# CH32F103C-R1.net
KiCad netlist of a schematic drawn in Altium Designer
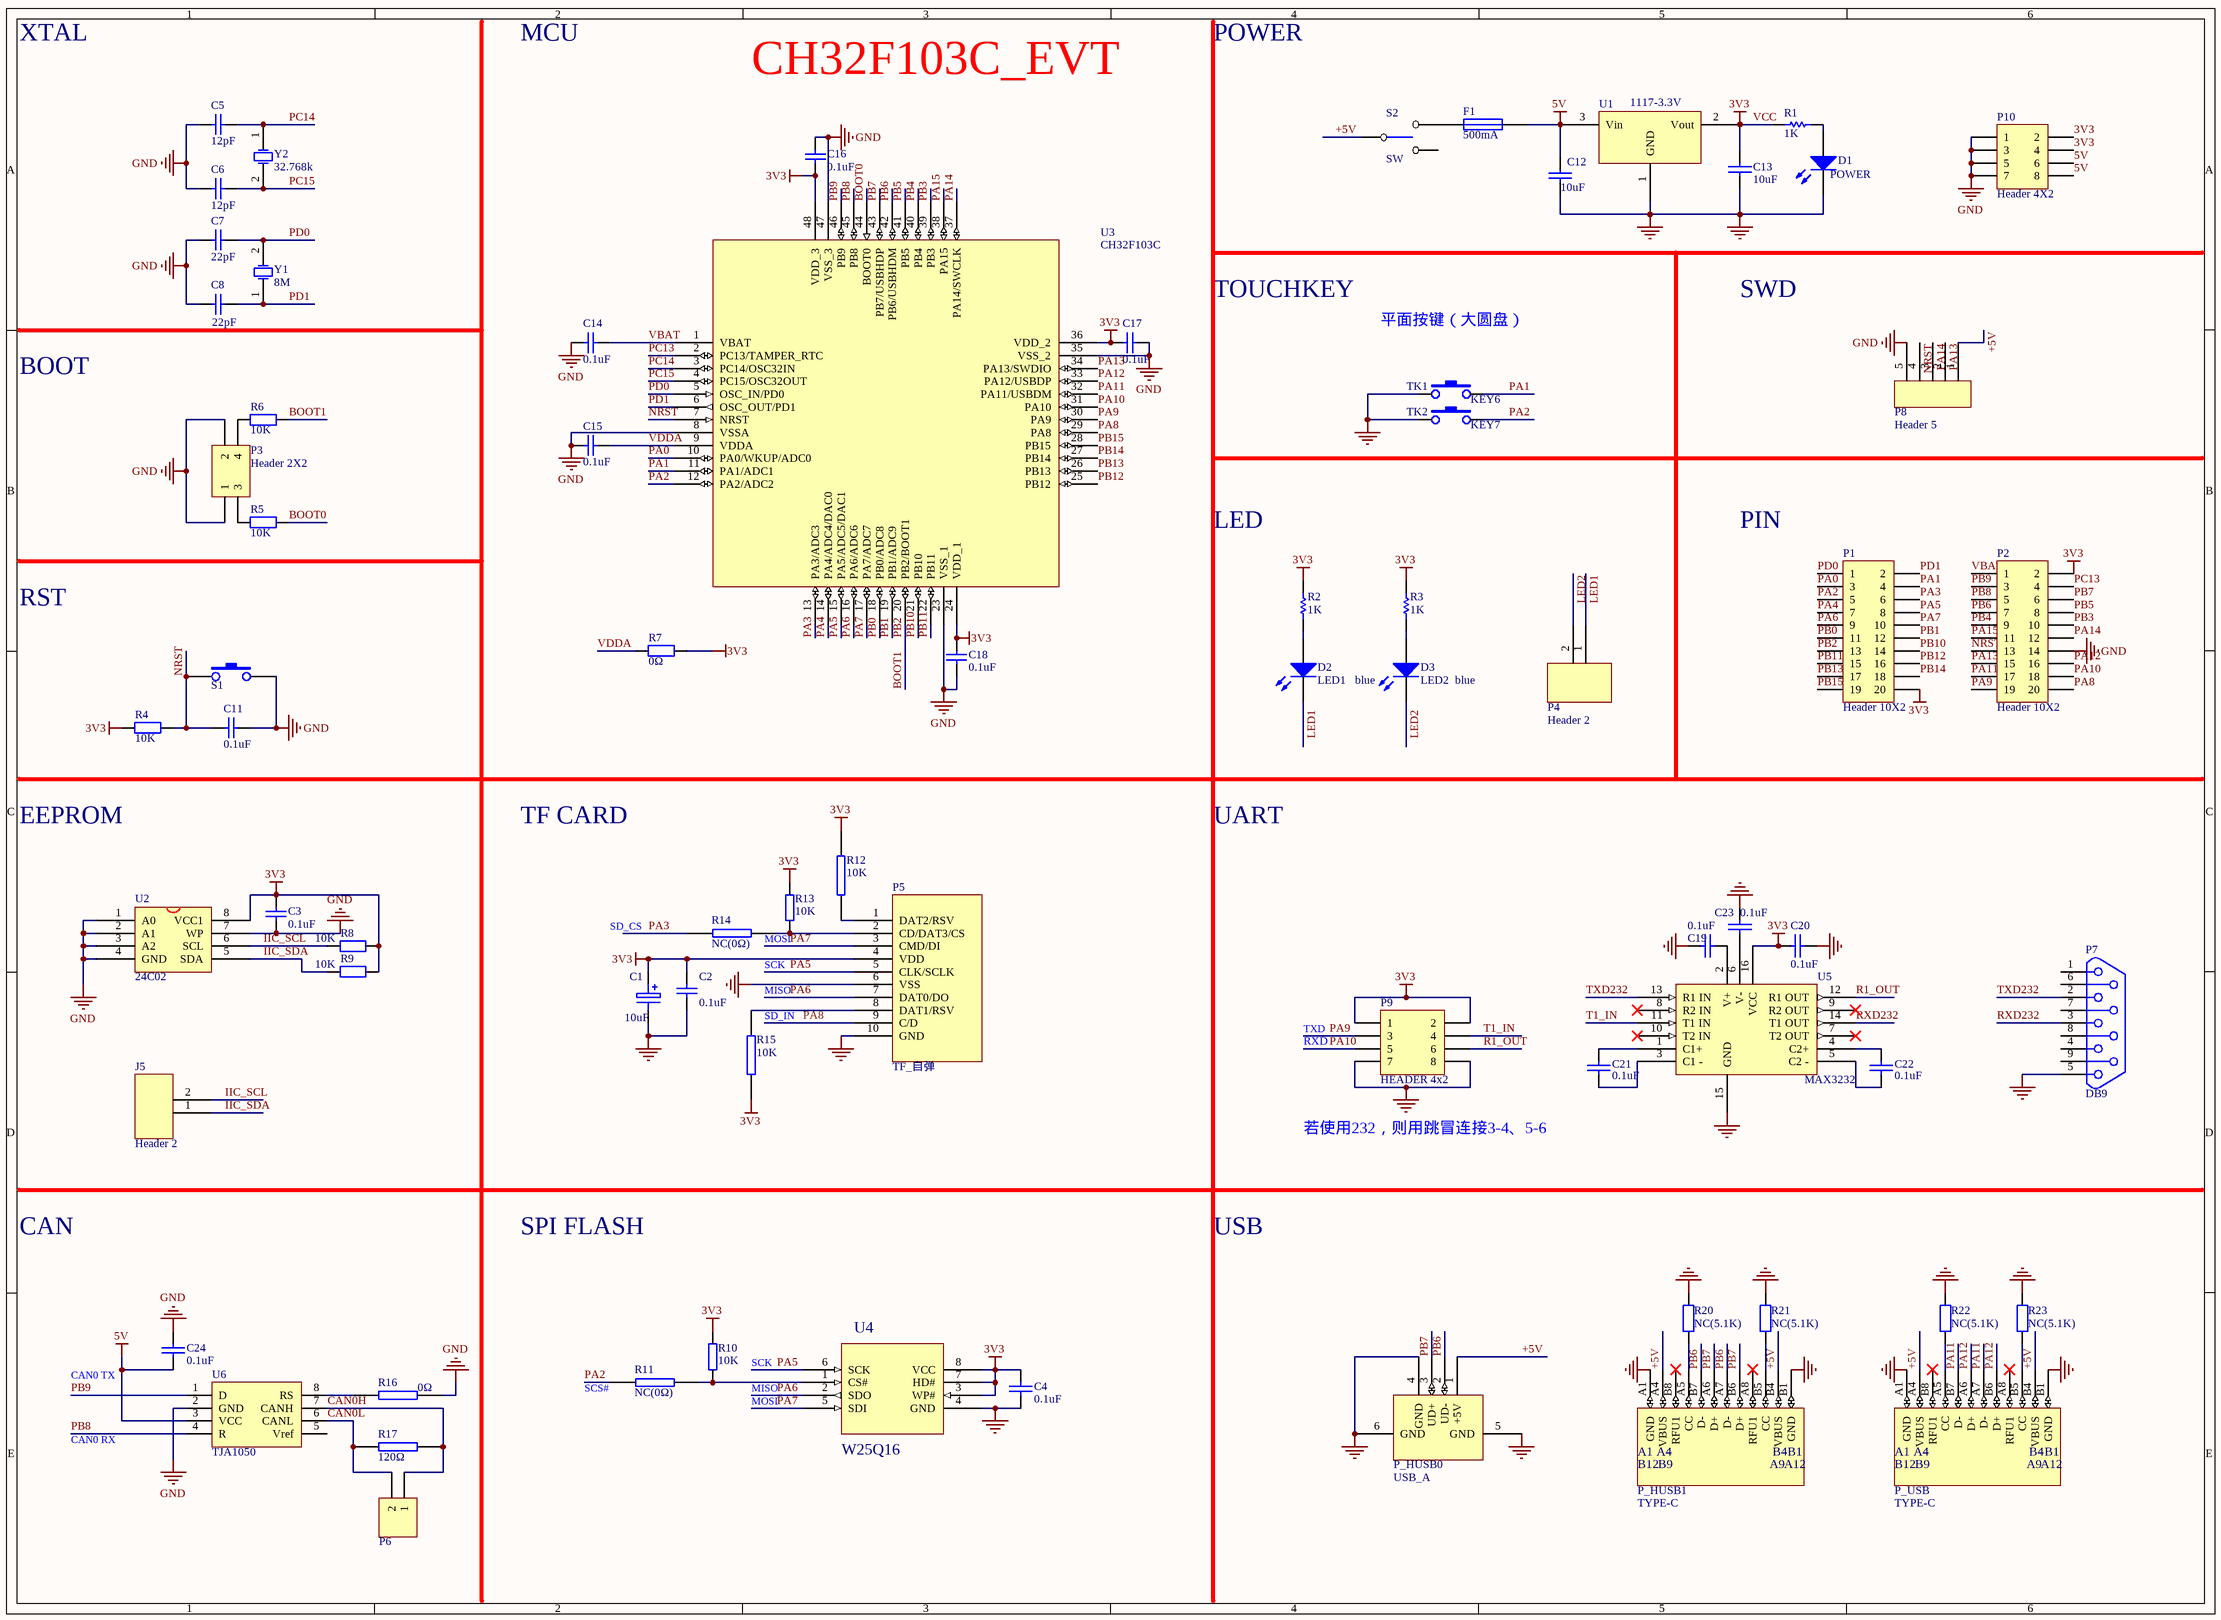
[diagram p0: CH32F103C-R1.SchDoc]

(export (version "E")
  (design (tool "Eeschema 10.0.6"))
  (components
    (comp (ref "C1")
      (value "10uF")
      (footprint "3216")
      (description "Electrolytic Capacitor")
      (libsource (lib "*") (part "ELECTRO1"))
    )
    (comp (ref "C2")
      (value "0.1uF")
      (footprint "0603")
      (description "Capacitor")
      (fields (field (name "PUBLISHER") "Altium Limited"))
      (libsource (lib "*") (part "Cap"))
    )
    (comp (ref "C3")
      (value "0.1uF")
      (footprint "0603")
      (description "Capacitor")
      (fields (field (name "PUBLISHER") "Altium Limited"))
      (libsource (lib "Miscellaneous Devices") (part "Cap"))
    )
    (comp (ref "C4")
      (value "0.1uF")
      (footprint "0603")
      (description "Capacitor")
      (libsource (lib "") (part "CAP_1"))
    )
    (comp (ref "C5")
      (value "12pF")
      (footprint "0603")
      (description "Capacitor")
      (fields (field (name "PUBLISHER") "Altium Limited"))
      (libsource (lib "Miscellaneous Devices") (part "Cap"))
    )
    (comp (ref "C6")
      (value "12pF")
      (footprint "0603")
      (description "Capacitor")
      (fields (field (name "PUBLISHER") "Altium Limited"))
      (libsource (lib "Miscellaneous Devices") (part "Cap"))
    )
    (comp (ref "C7")
      (value "22pF")
      (footprint "0603")
      (description "Capacitor")
      (fields (field (name "PUBLISHER") "Altium Limited"))
      (libsource (lib "Miscellaneous Devices") (part "Cap"))
    )
    (comp (ref "C8")
      (value "22pF")
      (footprint "0603")
      (description "Capacitor")
      (fields (field (name "PUBLISHER") "Altium Limited"))
      (libsource (lib "Miscellaneous Devices") (part "Cap"))
    )
    (comp (ref "C11")
      (value "0.1uF")
      (footprint "0603")
      (description "Capacitor")
      (fields (field (name "PUBLISHER") "Altium Limited"))
      (libsource (lib "Miscellaneous Devices") (part "Cap"))
    )
    (comp (ref "C12")
      (value "10uF")
      (footprint "3216")
      (description "Capacitor")
      (libsource (lib "*") (part "CAP"))
    )
    (comp (ref "C13")
      (value "10uF")
      (footprint "0603")
      (description "Capacitor")
      (libsource (lib "*") (part "CAP"))
    )
    (comp (ref "C14")
      (value "0.1uF")
      (footprint "0603")
      (description "Capacitor")
      (fields (field (name "PUBLISHER") "Altium Limited"))
      (libsource (lib "Miscellaneous Devices") (part "Cap"))
    )
    (comp (ref "C15")
      (value "0.1uF")
      (footprint "0603")
      (description "Capacitor")
      (fields (field (name "PUBLISHER") "Altium Limited"))
      (libsource (lib "Miscellaneous Devices") (part "Cap"))
    )
    (comp (ref "C16")
      (value "0.1uF")
      (footprint "0603")
      (description "Capacitor")
      (fields (field (name "PUBLISHER") "Altium Limited"))
      (libsource (lib "Miscellaneous Devices") (part "Cap"))
    )
    (comp (ref "C17")
      (value "0.1uF")
      (footprint "0603")
      (description "Capacitor")
      (fields (field (name "PUBLISHER") "Altium Limited"))
      (libsource (lib "Miscellaneous Devices") (part "Cap"))
    )
    (comp (ref "C18")
      (value "0.1uF")
      (footprint "0603")
      (description "Capacitor")
      (fields (field (name "PUBLISHER") "Altium Limited"))
      (libsource (lib "Miscellaneous Devices") (part "Cap"))
    )
    (comp (ref "C19")
      (value "0.1uF")
      (footprint "0603")
      (description "Capacitor")
      (libsource (lib "") (part "CAP_1"))
    )
    (comp (ref "C20")
      (value "0.1uF")
      (footprint "0603")
      (description "Capacitor")
      (libsource (lib "") (part "CAP_1"))
    )
    (comp (ref "C21")
      (value "0.1uF")
      (footprint "0603")
      (description "Capacitor")
      (libsource (lib "") (part "CAP_1"))
    )
    (comp (ref "C22")
      (value "0.1uF")
      (footprint "0603")
      (description "Capacitor")
      (libsource (lib "") (part "CAP_1"))
    )
    (comp (ref "C23")
      (value "0.1uF")
      (footprint "0603")
      (description "Capacitor")
      (libsource (lib "") (part "CAP_1"))
    )
    (comp (ref "C24")
      (value "0.1uF")
      (footprint "0603")
      (description "Capacitor")
      (libsource (lib "") (part "CAP_1"))
    )
    (comp (ref "D1")
      (value "POWER")
      (footprint "0603L")
      (description "Typical INFRARED GaAs LED")
      (fields (field (name "PUBLISHER") "Altium Limited"))
      (libsource (lib "Miscellaneous Devices") (part "LED0"))
    )
    (comp (ref "D2")
      (value "LED1   blue")
      (footprint "0603L")
      (description "Typical INFRARED GaAs LED")
      (fields (field (name "PUBLISHER") "Altium Limited"))
      (libsource (lib "Miscellaneous Devices") (part "LED0"))
    )
    (comp (ref "D3")
      (value "LED2  blue")
      (footprint "0603L")
      (description "Typical INFRARED GaAs LED")
      (fields (field (name "PUBLISHER") "Altium Limited"))
      (libsource (lib "Miscellaneous Devices") (part "LED0"))
    )
    (comp (ref "F1")
      (value "500mA")
      (footprint "0603")
      (description "Fuse")
      (libsource (lib "*") (part "FUSE1"))
    )
    (comp (ref "J5") (value "Header 2") (footprint "SIP2 - 40mil") (libsource (lib "") (part "2HEAD_1")))
    (comp (ref "P1")
      (value "Header 10X2")
      (footprint "IDC20")
      (description "Header, 10-Pin, Dual row")
      (fields (field (name "PUBLISHER") "Altium Limited"))
      (libsource (lib "Miscellaneous Connectors") (part "Header 10X2"))
    )
    (comp (ref "P2")
      (value "Header 10X2")
      (footprint "IDC20")
      (description "Header, 10-Pin, Dual row")
      (fields (field (name "PUBLISHER") "Altium Limited"))
      (libsource (lib "Miscellaneous Connectors") (part "Header 10X2"))
    )
    (comp (ref "P3")
      (value "Header 2X2")
      (footprint "HDR2X2")
      (description "Header, 2-Pin, Dual row")
      (fields (field (name "PUBLISHER") "Altium Limited"))
      (libsource (lib "Miscellaneous Connectors") (part "Header 2X2"))
    )
    (comp (ref "P4") (value "Header 2") (footprint "SIP2 - 40mil") (libsource (lib "MYSCH") (part "2HEAD")))
    (comp (ref "P5") (value "TF_自弹") (footprint "TF_CARD") (libsource (lib "*") (part "TF_自弹")))
    (comp (ref "P6")
      (value "Header 2")
      (footprint "PORT2 4.5MM")
      (description "Header, 2-Pin")
      (fields (field (name "PUBLISHER") "Altium Limited"))
      (libsource (lib "Miscellaneous Connectors") (part "Header 2"))
    )
    (comp (ref "P7") (value "DB9") (footprint "DB9") (libsource (lib "*") (part "DB9")))
    (comp (ref "P8")
      (value "Header 5")
      (footprint "SIP5 - 40mil")
      (libsource (lib "PCB_Project1") (part "2HEAD"))
    )
    (comp (ref "P9")
      (value "HEADER 4x2")
      (footprint "MYPCB:IDC8-2.54mm")
      (description "Header, 4-Pin, Dual row")
      (libsource (lib "wch_sch_others") (part "HEADER 4x2"))
    )
    (comp (ref "P10")
      (value "Header 4X2")
      (footprint "IDC8")
      (description "Header, 4-Pin, Dual row")
      (fields (field (name "PUBLISHER") "Altium Limited"))
      (libsource (lib "Miscellaneous Connectors") (part "Header 4X2"))
    )
    (comp (ref "P_HUSB0")
      (value "USB_A")
      (footprint "USBA-l")
      (description "USB Port")
      (libsource (lib "CHXXXSCH") (part "USB"))
    )
    (comp (ref "P_HUSB1")
      (value "TYPE-C")
      (footprint "TYPE-C-Receptacle-2.0")
      (libsource (lib "*") (part "TYPE-C1"))
    )
    (comp (ref "P_USB")
      (value "TYPE-C")
      (footprint "TYPE-C-Receptacle-2.0")
      (libsource (lib "*") (part "TYPE-C1"))
    )
    (comp (ref "R1")
      (value "1K")
      (footprint "0603")
      (description "Semiconductor Resistor")
      (fields (field (name "PUBLISHER") "Altium Limited"))
      (libsource (lib "Miscellaneous Devices") (part "Res Semi"))
    )
    (comp (ref "R2")
      (value "1K")
      (footprint "0603")
      (description "Semiconductor Resistor")
      (fields (field (name "PUBLISHER") "Altium Limited"))
      (libsource (lib "Miscellaneous Devices") (part "Res Semi"))
    )
    (comp (ref "R3")
      (value "1K")
      (footprint "0603")
      (description "Semiconductor Resistor")
      (fields (field (name "PUBLISHER") "Altium Limited"))
      (libsource (lib "Miscellaneous Devices") (part "Res Semi"))
    )
    (comp (ref "R4")
      (value "10K")
      (footprint "0603")
      (description "Resistor")
      (fields (field (name "PUBLISHER") "Altium Limited"))
      (libsource (lib "") (part "Res2_1"))
    )
    (comp (ref "R5")
      (value "10K")
      (footprint "0603")
      (description "Resistor")
      (fields (field (name "PUBLISHER") "Altium Limited"))
      (libsource (lib "") (part "Res2_1"))
    )
    (comp (ref "R6")
      (value "10K")
      (footprint "0603")
      (description "Resistor")
      (fields (field (name "PUBLISHER") "Altium Limited"))
      (libsource (lib "") (part "Res2_1"))
    )
    (comp (ref "R7")
      (value "0Ω")
      (footprint "0603")
      (description "Resistor")
      (fields (field (name "PUBLISHER") "Altium Limited"))
      (libsource (lib "") (part "Res2_1"))
    )
    (comp (ref "R8")
      (value "10K")
      (footprint "0603")
      (description "Resistor")
      (fields (field (name "PUBLISHER") "Altium Limited"))
      (libsource (lib "") (part "Res2_1"))
    )
    (comp (ref "R9")
      (value "10K")
      (footprint "0603")
      (description "Resistor")
      (fields (field (name "PUBLISHER") "Altium Limited"))
      (libsource (lib "") (part "Res2_1"))
    )
    (comp (ref "R10") (value "10K") (footprint "0603") (libsource (lib "*") (part "DZ")))
    (comp (ref "R11") (value "NC(0Ω)") (footprint "0603") (libsource (lib "*") (part "RES2")))
    (comp (ref "R12") (value "10K") (footprint "0603") (libsource (lib "*") (part "RES2")))
    (comp (ref "R13") (value "10K") (footprint "0603") (libsource (lib "*") (part "DZ")))
    (comp (ref "R14") (value "NC(0Ω)") (footprint "0603") (libsource (lib "*") (part "RES2")))
    (comp (ref "R15") (value "10K") (footprint "0603") (libsource (lib "*") (part "RES2")))
    (comp (ref "R16") (value "0Ω") (footprint "0603") (libsource (lib "*") (part "RES2")))
    (comp (ref "R17") (value "120Ω") (footprint "0603") (libsource (lib "*") (part "RES2")))
    (comp (ref "R20")
      (value "NC(5.1K)")
      (footprint "0603")
      (description "Resistor")
      (libsource (lib "Miscellaneous Devices") (part "Res2"))
    )
    (comp (ref "R21")
      (value "NC(5.1K)")
      (footprint "0603")
      (description "Resistor")
      (libsource (lib "Miscellaneous Devices") (part "Res2"))
    )
    (comp (ref "R22")
      (value "NC(5.1K)")
      (footprint "0603")
      (description "Resistor")
      (libsource (lib "Miscellaneous Devices") (part "Res2"))
    )
    (comp (ref "R23")
      (value "NC(5.1K)")
      (footprint "0603")
      (description "Resistor")
      (libsource (lib "Miscellaneous Devices") (part "Res2"))
    )
    (comp (ref "S1") (value "KEY") (footprint "贴片按键") (libsource (lib "CCDXPLIB") (part "KEY")))
    (comp (ref "S2") (value "SW") (footprint "KEY2") (libsource (lib "MYSCH") (part "SW")))
    (comp (ref "TK1") (value "KEY6") (footprint "KEY68") (libsource (lib "*") (part "KEY")))
    (comp (ref "TK2") (value "KEY7") (footprint "KEY68") (libsource (lib "*") (part "KEY")))
    (comp (ref "U1")
      (value "1117-3.3V")
      (footprint "SOT-223")
      (libsource (lib "wch_sch_others") (part "1117-3.3V"))
    )
    (comp (ref "U2") (value "24C02") (footprint "SOP8") (libsource (lib "Elite_SCH") (part "24C256")))
    (comp (ref "U3")
      (value "CH32F103C")
      (footprint "LQFP48")
      (description "ARM M3 MCU with USB device & USB host & ADC & 12bit DAC & Touch Key & CAN")
      (libsource (lib "CHXXX") (part "CH32F103C"))
    )
    (comp (ref "U4")
      (value "W25Q16")
      (footprint "016 SO-8")
      (libsource (lib "*") (part "Pro89C.tmp_25F512_2"))
    )
    (comp (ref "U5")
      (value "MAX3232")
      (footprint "SO-16")
      (description "+-15KV ESD-PROTECTED, +5V RS-232 TRANSCEIVERS")
      (libsource (lib "*") (part "MAX232CPE(16)"))
    )
    (comp (ref "U6") (value "TJA1050") (footprint "SOP8") (libsource (lib "CAN") (part "Component_1")))
    (comp (ref "Y1")
      (value "8M")
      (footprint "XT62/28")
      (description "Crystal Oscillator")
      (fields (field (name "PUBLISHER") "Altium Limited"))
      (libsource (lib "Miscellaneous Devices") (part "XTAL"))
    )
    (comp (ref "Y2")
      (value "32.768k")
      (footprint "FC-135")
      (description "Crystal Oscillator")
      (fields (field (name "PUBLISHER") "Altium Limited"))
      (libsource (lib "Miscellaneous Devices") (part "XTAL"))
    )
  )
  (nets
    (net (code "1") (name "/+5V") (class "Default")
      (node (ref "P8") (pin "1") (pintype "passive"))
      (node (ref "P_HUSB0") (pin "1") (pinfunction "+5V_1") (pintype "power_in"))
      (node (ref "P_HUSB1") (pin "A4") (pinfunction "VBUS_A4") (pintype "bidirectional"))
      (node (ref "P_HUSB1") (pin "B4") (pinfunction "VBUS_B4") (pintype "bidirectional"))
      (node (ref "P_USB") (pin "A4") (pinfunction "VBUS_A4") (pintype "bidirectional"))
      (node (ref "P_USB") (pin "B4") (pinfunction "VBUS_B4") (pintype "bidirectional"))
      (node (ref "S2") (pin "1") (pinfunction "1_1") (pintype "passive"))
    )
    (net (code "3") (name "/BOOT0") (class "Default")
      (node (ref "R5") (pin "1") (pinfunction "1_1") (pintype "passive"))
      (node (ref "U3") (pin "44") (pinfunction "BOOT0_44") (pintype "input"))
    )
    (net (code "4") (name "/BOOT1") (class "Default")
      (node (ref "P1") (pin "13") (pinfunction "13_13") (pintype "passive"))
      (node (ref "R6") (pin "1") (pinfunction "1_1") (pintype "passive"))
      (node (ref "U3") (pin "20") (pinfunction "PB2/BOOT1_20") (pintype "bidirectional"))
    )
    (net (code "5") (name "/CAN0H") (class "Default")
      (node (ref "P6") (pin "1") (pinfunction "1_1") (pintype "passive"))
      (node (ref "R17") (pin "1") (pinfunction "1_1") (pintype "passive"))
      (node (ref "U6") (pin "7") (pinfunction "CANH_7") (pintype "passive"))
    )
    (net (code "6") (name "/CAN0L") (class "Default")
      (node (ref "P6") (pin "2") (pinfunction "2_2") (pintype "passive"))
      (node (ref "R17") (pin "2") (pinfunction "2_2") (pintype "passive"))
      (node (ref "U6") (pin "6") (pinfunction "CANL_6") (pintype "passive"))
    )
    (net (code "7") (name "/IIC_SCL") (class "Default")
      (node (ref "J5") (pin "2") (pintype "passive"))
      (node (ref "R8") (pin "2") (pinfunction "2_2") (pintype "passive"))
      (node (ref "U2") (pin "6") (pinfunction "SCL_6") (pintype "passive"))
    )
    (net (code "8") (name "/IIC_SDA") (class "Default")
      (node (ref "J5") (pin "1") (pintype "passive"))
      (node (ref "R9") (pin "2") (pinfunction "2_2") (pintype "passive"))
      (node (ref "U2") (pin "5") (pinfunction "SDA_5") (pintype "passive"))
    )
    (net (code "9") (name "/LED1") (class "Default")
      (node (ref "D2") (pin "2") (pinfunction "K_2") (pintype "passive"))
      (node (ref "P4") (pin "1") (pintype "passive"))
    )
    (net (code "10") (name "/LED2") (class "Default")
      (node (ref "D3") (pin "2") (pinfunction "K_2") (pintype "passive"))
      (node (ref "P4") (pin "2") (pintype "passive"))
    )
    (net (code "11") (name "/NRST") (class "Default")
      (node (ref "C11") (pin "2") (pinfunction "2_2") (pintype "passive"))
      (node (ref "P2") (pin "13") (pinfunction "13_13") (pintype "passive"))
      (node (ref "P8") (pin "4") (pintype "passive"))
      (node (ref "R4") (pin "1") (pinfunction "1_1") (pintype "passive"))
      (node (ref "S1") (pin "1") (pinfunction "1_1") (pintype "passive"))
      (node (ref "U3") (pin "7") (pinfunction "NRST_7") (pintype "input"))
    )
    (net (code "12") (name "/PA0") (class "Default")
      (node (ref "P1") (pin "3") (pinfunction "3_3") (pintype "passive"))
      (node (ref "U3") (pin "10") (pinfunction "PA0/WKUP/ADC0_10") (pintype "bidirectional"))
    )
    (net (code "13") (name "/PA1") (class "Default")
      (node (ref "P1") (pin "4") (pinfunction "4_4") (pintype "passive"))
      (node (ref "TK1") (pin "1") (pintype "passive"))
      (node (ref "U3") (pin "11") (pinfunction "PA1/ADC1_11") (pintype "bidirectional"))
    )
    (net (code "14") (name "/PA2") (class "Default")
      (node (ref "P1") (pin "5") (pinfunction "5_5") (pintype "passive"))
      (node (ref "R11") (pin "2") (pinfunction "2_2") (pintype "passive"))
      (node (ref "TK2") (pin "1") (pintype "passive"))
      (node (ref "U3") (pin "12") (pinfunction "PA2/ADC2_12") (pintype "bidirectional"))
    )
    (net (code "15") (name "/PA3") (class "Default")
      (node (ref "P1") (pin "6") (pinfunction "6_6") (pintype "passive"))
      (node (ref "R14") (pin "2") (pinfunction "2_2") (pintype "passive"))
      (node (ref "U3") (pin "13") (pinfunction "PA3/ADC3_13") (pintype "bidirectional"))
    )
    (net (code "16") (name "/PA4") (class "Default")
      (node (ref "P1") (pin "7") (pinfunction "7_7") (pintype "passive"))
      (node (ref "U3") (pin "14") (pinfunction "PA4/ADC4/DAC0_14") (pintype "bidirectional"))
    )
    (net (code "17") (name "/PA5") (class "Default")
      (node (ref "P1") (pin "8") (pinfunction "8_8") (pintype "passive"))
      (node (ref "P5") (pin "5") (pinfunction "CLK/SCLK_5") (pintype "passive"))
      (node (ref "U3") (pin "15") (pinfunction "PA5/ADC5/DAC1_15") (pintype "bidirectional"))
      (node (ref "U4") (pin "6") (pinfunction "SCK_6") (pintype "input"))
    )
    (net (code "18") (name "/PA6") (class "Default")
      (node (ref "P1") (pin "9") (pinfunction "9_9") (pintype "passive"))
      (node (ref "P5") (pin "7") (pinfunction "DAT0/DO_7") (pintype "passive"))
      (node (ref "U3") (pin "16") (pinfunction "PA6/ADC6_16") (pintype "bidirectional"))
      (node (ref "U4") (pin "2") (pinfunction "SDO_2") (pintype "output"))
    )
    (net (code "19") (name "/PA7") (class "Default")
      (node (ref "P1") (pin "10") (pinfunction "10_10") (pintype "passive"))
      (node (ref "P5") (pin "3") (pinfunction "CMD/DI_3") (pintype "passive"))
      (node (ref "U3") (pin "17") (pinfunction "PA7/ADC7_17") (pintype "bidirectional"))
      (node (ref "U4") (pin "5") (pinfunction "SDI_5") (pintype "input"))
    )
    (net (code "20") (name "/PA8") (class "Default")
      (node (ref "P2") (pin "20") (pinfunction "20_20") (pintype "passive"))
      (node (ref "P5") (pin "9") (pinfunction "C/D_9") (pintype "passive"))
      (node (ref "U3") (pin "29") (pinfunction "PA8_29") (pintype "bidirectional"))
    )
    (net (code "21") (name "/PA9") (class "Default")
      (node (ref "P2") (pin "19") (pinfunction "19_19") (pintype "passive"))
      (node (ref "P9") (pin "3") (pinfunction "3_3") (pintype "passive"))
      (node (ref "U3") (pin "30") (pinfunction "PA9_30") (pintype "bidirectional"))
    )
    (net (code "22") (name "/PA10") (class "Default")
      (node (ref "P2") (pin "18") (pinfunction "18_18") (pintype "passive"))
      (node (ref "P9") (pin "5") (pinfunction "5_5") (pintype "passive"))
      (node (ref "U3") (pin "31") (pinfunction "PA10_31") (pintype "bidirectional"))
    )
    (net (code "23") (name "/PA11") (class "Default")
      (node (ref "P2") (pin "17") (pinfunction "17_17") (pintype "passive"))
      (node (ref "P_USB") (pin "A7") (pinfunction "D-_A7") (pintype "bidirectional"))
      (node (ref "P_USB") (pin "B7") (pinfunction "D-_B7") (pintype "bidirectional"))
      (node (ref "U3") (pin "32") (pinfunction "PA11/USBDM_32") (pintype "bidirectional"))
    )
    (net (code "24") (name "/PA12") (class "Default")
      (node (ref "P2") (pin "16") (pinfunction "16_16") (pintype "passive"))
      (node (ref "P_USB") (pin "A6") (pinfunction "D+_A6") (pintype "bidirectional"))
      (node (ref "P_USB") (pin "B6") (pinfunction "D+_B6") (pintype "bidirectional"))
      (node (ref "U3") (pin "33") (pinfunction "PA12/USBDP_33") (pintype "bidirectional"))
    )
    (net (code "25") (name "/PA13") (class "Default")
      (node (ref "P2") (pin "15") (pinfunction "15_15") (pintype "passive"))
      (node (ref "P8") (pin "2") (pintype "passive"))
      (node (ref "U3") (pin "34") (pinfunction "PA13/SWDIO_34") (pintype "bidirectional"))
    )
    (net (code "26") (name "/PA14") (class "Default")
      (node (ref "P2") (pin "12") (pinfunction "12_12") (pintype "passive"))
      (node (ref "P8") (pin "3") (pintype "passive"))
      (node (ref "U3") (pin "37") (pinfunction "PA14/SWCLK_37") (pintype "bidirectional"))
    )
    (net (code "27") (name "/PA15") (class "Default")
      (node (ref "P2") (pin "11") (pinfunction "11_11") (pintype "passive"))
      (node (ref "U3") (pin "38") (pinfunction "PA15_38") (pintype "bidirectional"))
    )
    (net (code "28") (name "/PB0") (class "Default")
      (node (ref "P1") (pin "11") (pinfunction "11_11") (pintype "passive"))
      (node (ref "U3") (pin "18") (pinfunction "PB0/ADC8_18") (pintype "bidirectional"))
    )
    (net (code "29") (name "/PB1") (class "Default")
      (node (ref "P1") (pin "12") (pinfunction "12_12") (pintype "passive"))
      (node (ref "U3") (pin "19") (pinfunction "PB1/ADC9_19") (pintype "bidirectional"))
    )
    (net (code "30") (name "/PB3") (class "Default")
      (node (ref "P2") (pin "10") (pinfunction "10_10") (pintype "passive"))
      (node (ref "U3") (pin "39") (pinfunction "PB3_39") (pintype "bidirectional"))
    )
    (net (code "31") (name "/PB4") (class "Default")
      (node (ref "P2") (pin "9") (pinfunction "9_9") (pintype "passive"))
      (node (ref "U3") (pin "40") (pinfunction "PB4_40") (pintype "bidirectional"))
    )
    (net (code "32") (name "/PB5") (class "Default")
      (node (ref "P2") (pin "8") (pinfunction "8_8") (pintype "passive"))
      (node (ref "U3") (pin "41") (pinfunction "PB5_41") (pintype "bidirectional"))
    )
    (net (code "33") (name "/PB6") (class "Default")
      (node (ref "P2") (pin "7") (pinfunction "7_7") (pintype "passive"))
      (node (ref "P_HUSB0") (pin "2") (pinfunction "UD-_2") (pintype "bidirectional"))
      (node (ref "P_HUSB1") (pin "A7") (pinfunction "D-_A7") (pintype "bidirectional"))
      (node (ref "P_HUSB1") (pin "B7") (pinfunction "D-_B7") (pintype "bidirectional"))
      (node (ref "U3") (pin "42") (pinfunction "PB6/USBHDM_42") (pintype "bidirectional"))
    )
    (net (code "34") (name "/PB7") (class "Default")
      (node (ref "P2") (pin "6") (pinfunction "6_6") (pintype "passive"))
      (node (ref "P_HUSB0") (pin "3") (pinfunction "UD+_3") (pintype "bidirectional"))
      (node (ref "P_HUSB1") (pin "A6") (pinfunction "D+_A6") (pintype "bidirectional"))
      (node (ref "P_HUSB1") (pin "B6") (pinfunction "D+_B6") (pintype "bidirectional"))
      (node (ref "U3") (pin "43") (pinfunction "PB7/USBHDP_43") (pintype "bidirectional"))
    )
    (net (code "35") (name "/PB8") (class "Default")
      (node (ref "P2") (pin "5") (pinfunction "5_5") (pintype "passive"))
      (node (ref "U3") (pin "45") (pinfunction "PB8_45") (pintype "bidirectional"))
      (node (ref "U6") (pin "4") (pinfunction "R_4") (pintype "passive"))
    )
    (net (code "36") (name "/PB9") (class "Default")
      (node (ref "P2") (pin "3") (pinfunction "3_3") (pintype "passive"))
      (node (ref "U3") (pin "46") (pinfunction "PB9_46") (pintype "bidirectional"))
      (node (ref "U6") (pin "1") (pinfunction "D_1") (pintype "passive"))
    )
    (net (code "37") (name "/PB10") (class "Default")
      (node (ref "P1") (pin "14") (pinfunction "14_14") (pintype "passive"))
      (node (ref "U3") (pin "21") (pinfunction "PB10_21") (pintype "bidirectional"))
    )
    (net (code "38") (name "/PB11") (class "Default")
      (node (ref "P1") (pin "15") (pinfunction "15_15") (pintype "passive"))
      (node (ref "U3") (pin "22") (pinfunction "PB11_22") (pintype "bidirectional"))
    )
    (net (code "39") (name "/PB12") (class "Default")
      (node (ref "P1") (pin "16") (pinfunction "16_16") (pintype "passive"))
      (node (ref "U3") (pin "25") (pinfunction "PB12_25") (pintype "bidirectional"))
    )
    (net (code "40") (name "/PB13") (class "Default")
      (node (ref "P1") (pin "17") (pinfunction "17_17") (pintype "passive"))
      (node (ref "U3") (pin "26") (pinfunction "PB13_26") (pintype "bidirectional"))
    )
    (net (code "41") (name "/PB14") (class "Default")
      (node (ref "P1") (pin "18") (pinfunction "18_18") (pintype "passive"))
      (node (ref "U3") (pin "27") (pinfunction "PB14_27") (pintype "bidirectional"))
    )
    (net (code "42") (name "/PB15") (class "Default")
      (node (ref "P1") (pin "19") (pinfunction "19_19") (pintype "passive"))
      (node (ref "U3") (pin "28") (pinfunction "PB15_28") (pintype "bidirectional"))
    )
    (net (code "43") (name "/PC13") (class "Default")
      (node (ref "P2") (pin "4") (pinfunction "4_4") (pintype "passive"))
      (node (ref "U3") (pin "2") (pinfunction "PC13/TAMPER_RTC_2") (pintype "bidirectional"))
    )
    (net (code "44") (name "/PC14") (class "Default")
      (node (ref "C5") (pin "1") (pinfunction "1_1") (pintype "passive"))
      (node (ref "U3") (pin "3") (pinfunction "PC14/OSC32IN_3") (pintype "bidirectional"))
      (node (ref "Y2") (pin "1") (pinfunction "OSC1_1") (pintype "passive"))
    )
    (net (code "45") (name "/PC15") (class "Default")
      (node (ref "C6") (pin "1") (pinfunction "1_1") (pintype "passive"))
      (node (ref "U3") (pin "4") (pinfunction "PC15/OSC32OUT_4") (pintype "bidirectional"))
      (node (ref "Y2") (pin "2") (pinfunction "OSC2_2") (pintype "passive"))
    )
    (net (code "46") (name "/PD0") (class "Default")
      (node (ref "C7") (pin "2") (pinfunction "2_2") (pintype "passive"))
      (node (ref "P1") (pin "1") (pinfunction "1_1") (pintype "passive"))
      (node (ref "U3") (pin "5") (pinfunction "OSC_IN/PD0_5") (pintype "input"))
      (node (ref "Y1") (pin "2") (pinfunction "OSC2_2") (pintype "passive"))
    )
    (net (code "47") (name "/PD1") (class "Default")
      (node (ref "C8") (pin "2") (pinfunction "2_2") (pintype "passive"))
      (node (ref "P1") (pin "2") (pinfunction "2_2") (pintype "passive"))
      (node (ref "U3") (pin "6") (pinfunction "OSC_OUT/PD1_6") (pintype "output"))
      (node (ref "Y1") (pin "1") (pinfunction "OSC1_1") (pintype "passive"))
    )
    (net (code "48") (name "/R1_OUT") (class "Default")
      (node (ref "P9") (pin "6") (pinfunction "6_6") (pintype "passive"))
      (node (ref "U5") (pin "12") (pinfunction "R1_OUT_12") (pintype "output"))
    )
    (net (code "49") (name "/RXD232") (class "Default")
      (node (ref "P7") (pin "3") (pinfunction "3_3") (pintype "passive"))
      (node (ref "U5") (pin "14") (pinfunction "T1_OUT_14") (pintype "output"))
    )
    (net (code "50") (name "/T1_IN") (class "Default")
      (node (ref "P9") (pin "4") (pinfunction "4_4") (pintype "passive"))
      (node (ref "U5") (pin "11") (pinfunction "T1_IN_11") (pintype "input"))
    )
    (net (code "51") (name "/TXD232") (class "Default")
      (node (ref "P7") (pin "2") (pinfunction "2_2") (pintype "passive"))
      (node (ref "U5") (pin "13") (pinfunction "R1_IN_13") (pintype "input"))
    )
    (net (code "52") (name "/VBAT") (class "Default")
      (node (ref "C14") (pin "1") (pinfunction "1_1") (pintype "passive"))
      (node (ref "P2") (pin "1") (pinfunction "1_1") (pintype "passive"))
      (node (ref "U3") (pin "1") (pinfunction "VBAT_1") (pintype "power_in"))
    )
    (net (code "53") (name "/VDDA") (class "Default")
      (node (ref "C15") (pin "1") (pinfunction "1_1") (pintype "passive"))
      (node (ref "R7") (pin "2") (pinfunction "2_2") (pintype "passive"))
      (node (ref "U3") (pin "9") (pinfunction "VDDA_9") (pintype "power_in"))
    )
    (net (code "54") (name "3V3") (class "Default")
      (node (ref "C1") (pin "1") (pinfunction "1_1") (pintype "passive"))
      (node (ref "C13") (pin "1") (pinfunction "1_1") (pintype "passive"))
      (node (ref "C16") (pin "2") (pinfunction "2_2") (pintype "passive"))
      (node (ref "C17") (pin "2") (pinfunction "2_2") (pintype "passive"))
      (node (ref "C18") (pin "2") (pinfunction "2_2") (pintype "passive"))
      (node (ref "C2") (pin "1") (pinfunction "1_1") (pintype "passive"))
      (node (ref "C20") (pin "2") (pinfunction "2_2") (pintype "passive"))
      (node (ref "C3") (pin "2") (pinfunction "2_2") (pintype "passive"))
      (node (ref "C4") (pin "2") (pinfunction "2_2") (pintype "passive"))
      (node (ref "P1") (pin "20") (pinfunction "20_20") (pintype "passive"))
      (node (ref "P10") (pin "2") (pinfunction "2_2") (pintype "passive"))
      (node (ref "P10") (pin "4") (pinfunction "4_4") (pintype "passive"))
      (node (ref "P2") (pin "2") (pinfunction "2_2") (pintype "passive"))
      (node (ref "P5") (pin "4") (pinfunction "VDD_4") (pintype "passive"))
      (node (ref "P9") (pin "1") (pinfunction "1_1") (pintype "passive"))
      (node (ref "P9") (pin "2") (pinfunction "2_2") (pintype "passive"))
      (node (ref "R1") (pin "2") (pinfunction "2_2") (pintype "passive"))
      (node (ref "R10") (pin "2") (pintype "passive"))
      (node (ref "R12") (pin "2") (pinfunction "2_2") (pintype "passive"))
      (node (ref "R13") (pin "2") (pintype "passive"))
      (node (ref "R15") (pin "1") (pinfunction "1_1") (pintype "passive"))
      (node (ref "R2") (pin "1") (pinfunction "1_1") (pintype "passive"))
      (node (ref "R3") (pin "1") (pinfunction "1_1") (pintype "passive"))
      (node (ref "R4") (pin "2") (pinfunction "2_2") (pintype "passive"))
      (node (ref "R7") (pin "1") (pinfunction "1_1") (pintype "passive"))
      (node (ref "R8") (pin "1") (pinfunction "1_1") (pintype "passive"))
      (node (ref "R9") (pin "1") (pinfunction "1_1") (pintype "passive"))
      (node (ref "U1") (pin "2") (pinfunction "Vout_2") (pintype "passive"))
      (node (ref "U2") (pin "8") (pinfunction "VCC1_8") (pintype "passive"))
      (node (ref "U3") (pin "24") (pinfunction "VDD_1_24") (pintype "power_in"))
      (node (ref "U3") (pin "36") (pinfunction "VDD_2_36") (pintype "power_in"))
      (node (ref "U3") (pin "48") (pinfunction "VDD_3_48") (pintype "power_in"))
      (node (ref "U4") (pin "3") (pinfunction "WP#_3") (pintype "input"))
      (node (ref "U4") (pin "7") (pinfunction "HD#_7") (pintype "power_in"))
      (node (ref "U4") (pin "8") (pinfunction "VCC_8") (pintype "power_in"))
      (node (ref "U5") (pin "16") (pinfunction "VCC_16") (pintype "power_in"))
    )
    (net (code "55") (name "5V") (class "Default")
      (node (ref "C12") (pin "1") (pinfunction "1_1") (pintype "passive"))
      (node (ref "C24") (pin "2") (pinfunction "2_2") (pintype "passive"))
      (node (ref "F1") (pin "2") (pinfunction "2_2") (pintype "passive"))
      (node (ref "P10") (pin "6") (pinfunction "6_6") (pintype "passive"))
      (node (ref "P10") (pin "8") (pinfunction "8_8") (pintype "passive"))
      (node (ref "U1") (pin "3") (pinfunction "Vin_3") (pintype "passive"))
      (node (ref "U6") (pin "3") (pinfunction "VCC_3") (pintype "passive"))
    )
    (net (code "56") (name "GND") (class "Default")
      (node (ref "C1") (pin "2") (pinfunction "2_2") (pintype "passive"))
      (node (ref "C11") (pin "1") (pinfunction "1_1") (pintype "passive"))
      (node (ref "C12") (pin "2") (pinfunction "2_2") (pintype "passive"))
      (node (ref "C13") (pin "2") (pinfunction "2_2") (pintype "passive"))
      (node (ref "C14") (pin "2") (pinfunction "2_2") (pintype "passive"))
      (node (ref "C15") (pin "2") (pinfunction "2_2") (pintype "passive"))
      (node (ref "C16") (pin "1") (pinfunction "1_1") (pintype "passive"))
      (node (ref "C17") (pin "1") (pinfunction "1_1") (pintype "passive"))
      (node (ref "C18") (pin "1") (pinfunction "1_1") (pintype "passive"))
      (node (ref "C19") (pin "2") (pinfunction "2_2") (pintype "passive"))
      (node (ref "C2") (pin "2") (pinfunction "2_2") (pintype "passive"))
      (node (ref "C20") (pin "1") (pinfunction "1_1") (pintype "passive"))
      (node (ref "C23") (pin "2") (pinfunction "2_2") (pintype "passive"))
      (node (ref "C24") (pin "1") (pinfunction "1_1") (pintype "passive"))
      (node (ref "C3") (pin "1") (pinfunction "1_1") (pintype "passive"))
      (node (ref "C4") (pin "1") (pinfunction "1_1") (pintype "passive"))
      (node (ref "C5") (pin "2") (pinfunction "2_2") (pintype "passive"))
      (node (ref "C6") (pin "2") (pinfunction "2_2") (pintype "passive"))
      (node (ref "C7") (pin "1") (pinfunction "1_1") (pintype "passive"))
      (node (ref "C8") (pin "1") (pinfunction "1_1") (pintype "passive"))
      (node (ref "D1") (pin "2") (pinfunction "K_2") (pintype "passive"))
      (node (ref "P10") (pin "1") (pinfunction "1_1") (pintype "passive"))
      (node (ref "P10") (pin "3") (pinfunction "3_3") (pintype "passive"))
      (node (ref "P10") (pin "5") (pinfunction "5_5") (pintype "passive"))
      (node (ref "P10") (pin "7") (pinfunction "7_7") (pintype "passive"))
      (node (ref "P2") (pin "14") (pinfunction "14_14") (pintype "passive"))
      (node (ref "P3") (pin "1") (pinfunction "1_1") (pintype "passive"))
      (node (ref "P3") (pin "2") (pinfunction "2_2") (pintype "passive"))
      (node (ref "P5") (pin "10") (pinfunction "GND_10") (pintype "passive"))
      (node (ref "P5") (pin "6") (pinfunction "VSS_6") (pintype "passive"))
      (node (ref "P7") (pin "5") (pinfunction "5_5") (pintype "passive"))
      (node (ref "P8") (pin "5") (pintype "passive"))
      (node (ref "P9") (pin "7") (pinfunction "7_7") (pintype "passive"))
      (node (ref "P9") (pin "8") (pinfunction "8_8") (pintype "passive"))
      (node (ref "P_HUSB0") (pin "4") (pinfunction "GND_4") (pintype "power_in"))
      (node (ref "P_HUSB0") (pin "5") (pinfunction "GND_5") (pintype "power_in"))
      (node (ref "P_HUSB0") (pin "6") (pinfunction "GND_6") (pintype "power_in"))
      (node (ref "P_HUSB1") (pin "A1") (pinfunction "GND_A1") (pintype "bidirectional"))
      (node (ref "P_HUSB1") (pin "B1") (pinfunction "GND_B1") (pintype "bidirectional"))
      (node (ref "P_USB") (pin "A1") (pinfunction "GND_A1") (pintype "bidirectional"))
      (node (ref "P_USB") (pin "B1") (pinfunction "GND_B1") (pintype "bidirectional"))
      (node (ref "R16") (pin "1") (pinfunction "1_1") (pintype "passive"))
      (node (ref "R20") (pin "2") (pinfunction "2_2") (pintype "passive"))
      (node (ref "R21") (pin "2") (pinfunction "2_2") (pintype "passive"))
      (node (ref "R22") (pin "2") (pinfunction "2_2") (pintype "passive"))
      (node (ref "R23") (pin "2") (pinfunction "2_2") (pintype "passive"))
      (node (ref "S1") (pin "3") (pinfunction "3_3") (pintype "passive"))
      (node (ref "TK1") (pin "3") (pintype "passive"))
      (node (ref "TK2") (pin "3") (pintype "passive"))
      (node (ref "U1") (pin "1") (pinfunction "GND_1") (pintype "passive"))
      (node (ref "U2") (pin "1") (pinfunction "A0_1") (pintype "passive"))
      (node (ref "U2") (pin "2") (pinfunction "A1_2") (pintype "passive"))
      (node (ref "U2") (pin "3") (pinfunction "A2_3") (pintype "passive"))
      (node (ref "U2") (pin "4") (pinfunction "GND_4") (pintype "passive"))
      (node (ref "U2") (pin "7") (pinfunction "WP_7") (pintype "passive"))
      (node (ref "U3") (pin "23") (pinfunction "VSS_1_23") (pintype "power_in"))
      (node (ref "U3") (pin "35") (pinfunction "VSS_2_35") (pintype "power_in"))
      (node (ref "U3") (pin "47") (pinfunction "VSS_3_47") (pintype "power_in"))
      (node (ref "U3") (pin "8") (pinfunction "VSSA_8") (pintype "power_in"))
      (node (ref "U4") (pin "4") (pinfunction "GND_4") (pintype "power_in"))
      (node (ref "U5") (pin "15") (pinfunction "GND_15") (pintype "power_in"))
      (node (ref "U6") (pin "2") (pinfunction "GND_2") (pintype "passive"))
    )
    (net (code "57") (name "Net-(D1-A)") (class "Default")
      (node (ref "D1") (pin "1") (pinfunction "A_1") (pintype "passive"))
      (node (ref "R1") (pin "1") (pinfunction "1_1") (pintype "passive"))
    )
    (net (code "58") (name "Net-(D2-A)") (class "Default")
      (node (ref "D2") (pin "1") (pinfunction "A_1") (pintype "passive"))
      (node (ref "R2") (pin "2") (pinfunction "2_2") (pintype "passive"))
    )
    (net (code "59") (name "Net-(D3-A)") (class "Default")
      (node (ref "D3") (pin "1") (pinfunction "A_1") (pintype "passive"))
      (node (ref "R3") (pin "2") (pinfunction "2_2") (pintype "passive"))
    )
    (net (code "60") (name "Net-(F1-Pad1)") (class "Default")
      (node (ref "F1") (pin "1") (pinfunction "1_1") (pintype "passive"))
      (node (ref "S2") (pin "2") (pinfunction "2_2") (pintype "passive"))
    )
    (net (code "61") (name "Net-(P3-Pad3)") (class "Default")
      (node (ref "P3") (pin "3") (pinfunction "3_3") (pintype "passive"))
      (node (ref "R5") (pin "2") (pinfunction "2_2") (pintype "passive"))
    )
    (net (code "62") (name "Net-(P3-Pad4)") (class "Default")
      (node (ref "P3") (pin "4") (pinfunction "4_4") (pintype "passive"))
      (node (ref "R6") (pin "2") (pinfunction "2_2") (pintype "passive"))
    )
    (net (code "63") (name "Net-(P5-CD{slash}DAT3{slash}CS)") (class "Default")
      (node (ref "P5") (pin "2") (pinfunction "CD/DAT3/CS_2") (pintype "passive"))
      (node (ref "R13") (pin "1") (pintype "passive"))
      (node (ref "R14") (pin "1") (pinfunction "1_1") (pintype "passive"))
    )
    (net (code "64") (name "Net-(P5-DAT1{slash}RSV)") (class "Default")
      (node (ref "P5") (pin "8") (pinfunction "DAT1/RSV_8") (pintype "passive"))
      (node (ref "R15") (pin "2") (pinfunction "2_2") (pintype "passive"))
    )
    (net (code "65") (name "Net-(P5-DAT2{slash}RSV)") (class "Default")
      (node (ref "P5") (pin "1") (pinfunction "DAT2/RSV_1") (pintype "passive"))
      (node (ref "R12") (pin "1") (pinfunction "1_1") (pintype "passive"))
    )
    (net (code "66") (name "Net-(P_HUSB1-CC-PadA5)") (class "Default")
      (node (ref "P_HUSB1") (pin "A5") (pinfunction "CC_A5") (pintype "bidirectional"))
      (node (ref "R20") (pin "1") (pinfunction "1_1") (pintype "passive"))
    )
    (net (code "67") (name "Net-(P_HUSB1-CC-PadB5)") (class "Default")
      (node (ref "P_HUSB1") (pin "B5") (pinfunction "CC_B5") (pintype "bidirectional"))
      (node (ref "R21") (pin "1") (pinfunction "1_1") (pintype "passive"))
    )
    (net (code "68") (name "Net-(P_USB-CC-PadA5)") (class "Default")
      (node (ref "P_USB") (pin "A5") (pinfunction "CC_A5") (pintype "bidirectional"))
      (node (ref "R22") (pin "1") (pinfunction "1_1") (pintype "passive"))
    )
    (net (code "69") (name "Net-(P_USB-CC-PadB5)") (class "Default")
      (node (ref "P_USB") (pin "B5") (pinfunction "CC_B5") (pintype "bidirectional"))
      (node (ref "R23") (pin "1") (pinfunction "1_1") (pintype "passive"))
    )
    (net (code "70") (name "Net-(U4-CS#)") (class "Default")
      (node (ref "R10") (pin "1") (pintype "passive"))
      (node (ref "R11") (pin "1") (pinfunction "1_1") (pintype "passive"))
      (node (ref "U4") (pin "1") (pinfunction "CS#_1") (pintype "input"))
    )
    (net (code "71") (name "Net-(U5-C1+)") (class "Default")
      (node (ref "C21") (pin "1") (pinfunction "1_1") (pintype "passive"))
      (node (ref "U5") (pin "1") (pinfunction "C1+_1") (pintype "passive"))
    )
    (net (code "72") (name "Net-(U5-C1_-)") (class "Default")
      (node (ref "C21") (pin "2") (pinfunction "2_2") (pintype "passive"))
      (node (ref "U5") (pin "3") (pinfunction "C1_-_3") (pintype "passive"))
    )
    (net (code "73") (name "Net-(U5-C2+)") (class "Default")
      (node (ref "C22") (pin "1") (pinfunction "1_1") (pintype "passive"))
      (node (ref "U5") (pin "4") (pinfunction "C2+_4") (pintype "passive"))
    )
    (net (code "74") (name "Net-(U5-C2_-)") (class "Default")
      (node (ref "C22") (pin "2") (pinfunction "2_2") (pintype "passive"))
      (node (ref "U5") (pin "5") (pinfunction "C2_-_5") (pintype "passive"))
    )
    (net (code "75") (name "Net-(U6-RS)") (class "Default")
      (node (ref "R16") (pin "2") (pinfunction "2_2") (pintype "passive"))
      (node (ref "U6") (pin "8") (pinfunction "RS_8") (pintype "passive"))
    )
    (net (code "76") (name "V+") (class "Default")
      (node (ref "C19") (pin "1") (pinfunction "1_1") (pintype "passive"))
      (node (ref "U5") (pin "2") (pinfunction "V+_2") (pintype "power_in"))
    )
    (net (code "77") (name "V-") (class "Default")
      (node (ref "C23") (pin "1") (pinfunction "1_1") (pintype "passive"))
      (node (ref "U5") (pin "6") (pinfunction "V-_6") (pintype "power_in"))
    )
    (net (code "78") (name "unconnected-(P7-Pad1)") (class "Default")
      (node (ref "P7") (pin "1") (pinfunction "1_1") (pintype "passive"))
    )
    (net (code "79") (name "unconnected-(P7-Pad4)") (class "Default")
      (node (ref "P7") (pin "4") (pinfunction "4_4") (pintype "passive"))
    )
    (net (code "80") (name "unconnected-(P7-Pad6)") (class "Default")
      (node (ref "P7") (pin "6") (pinfunction "6_6") (pintype "passive"))
    )
    (net (code "81") (name "unconnected-(P7-Pad7)") (class "Default")
      (node (ref "P7") (pin "7") (pinfunction "7_7") (pintype "passive"))
    )
    (net (code "82") (name "unconnected-(P7-Pad8)") (class "Default")
      (node (ref "P7") (pin "8") (pinfunction "8_8") (pintype "passive"))
    )
    (net (code "83") (name "unconnected-(P7-Pad9)") (class "Default")
      (node (ref "P7") (pin "9") (pinfunction "9_9") (pintype "passive"))
    )
    (net (code "84") (name "unconnected-(P_HUSB1-RFU1-PadA8)") (class "Default")
      (node (ref "P_HUSB1") (pin "A8") (pinfunction "RFU1_A8") (pintype "bidirectional+no_connect"))
    )
    (net (code "85") (name "unconnected-(P_HUSB1-RFU1-PadB8)") (class "Default")
      (node (ref "P_HUSB1") (pin "B8") (pinfunction "RFU1_B8") (pintype "bidirectional+no_connect"))
    )
    (net (code "86") (name "unconnected-(P_USB-RFU1-PadA8)") (class "Default")
      (node (ref "P_USB") (pin "A8") (pinfunction "RFU1_A8") (pintype "bidirectional+no_connect"))
    )
    (net (code "87") (name "unconnected-(P_USB-RFU1-PadB8)") (class "Default")
      (node (ref "P_USB") (pin "B8") (pinfunction "RFU1_B8") (pintype "bidirectional+no_connect"))
    )
    (net (code "88") (name "unconnected-(S2-Pad3)") (class "Default")
      (node (ref "S2") (pin "3") (pinfunction "3_3") (pintype "passive"))
    )
    (net (code "89") (name "unconnected-(U5-R2_IN-Pad8)") (class "Default")
      (node (ref "U5") (pin "8") (pinfunction "R2_IN_8") (pintype "input+no_connect"))
    )
    (net (code "90") (name "unconnected-(U5-R2_OUT-Pad9)") (class "Default")
      (node (ref "U5") (pin "9") (pinfunction "R2_OUT_9") (pintype "output+no_connect"))
    )
    (net (code "91") (name "unconnected-(U5-T2_IN-Pad10)") (class "Default")
      (node (ref "U5") (pin "10") (pinfunction "T2_IN_10") (pintype "input+no_connect"))
    )
    (net (code "92") (name "unconnected-(U5-T2_OUT-Pad7)") (class "Default")
      (node (ref "U5") (pin "7") (pinfunction "T2_OUT_7") (pintype "output+no_connect"))
    )
    (net (code "93") (name "unconnected-(U6-Vref-Pad5)") (class "Default")
      (node (ref "U6") (pin "5") (pinfunction "Vref_5") (pintype "passive"))
    )
  )
)
